# sensorboard_radiation_rev0.net
KiCad netlist of a schematic drawn in EAGLE
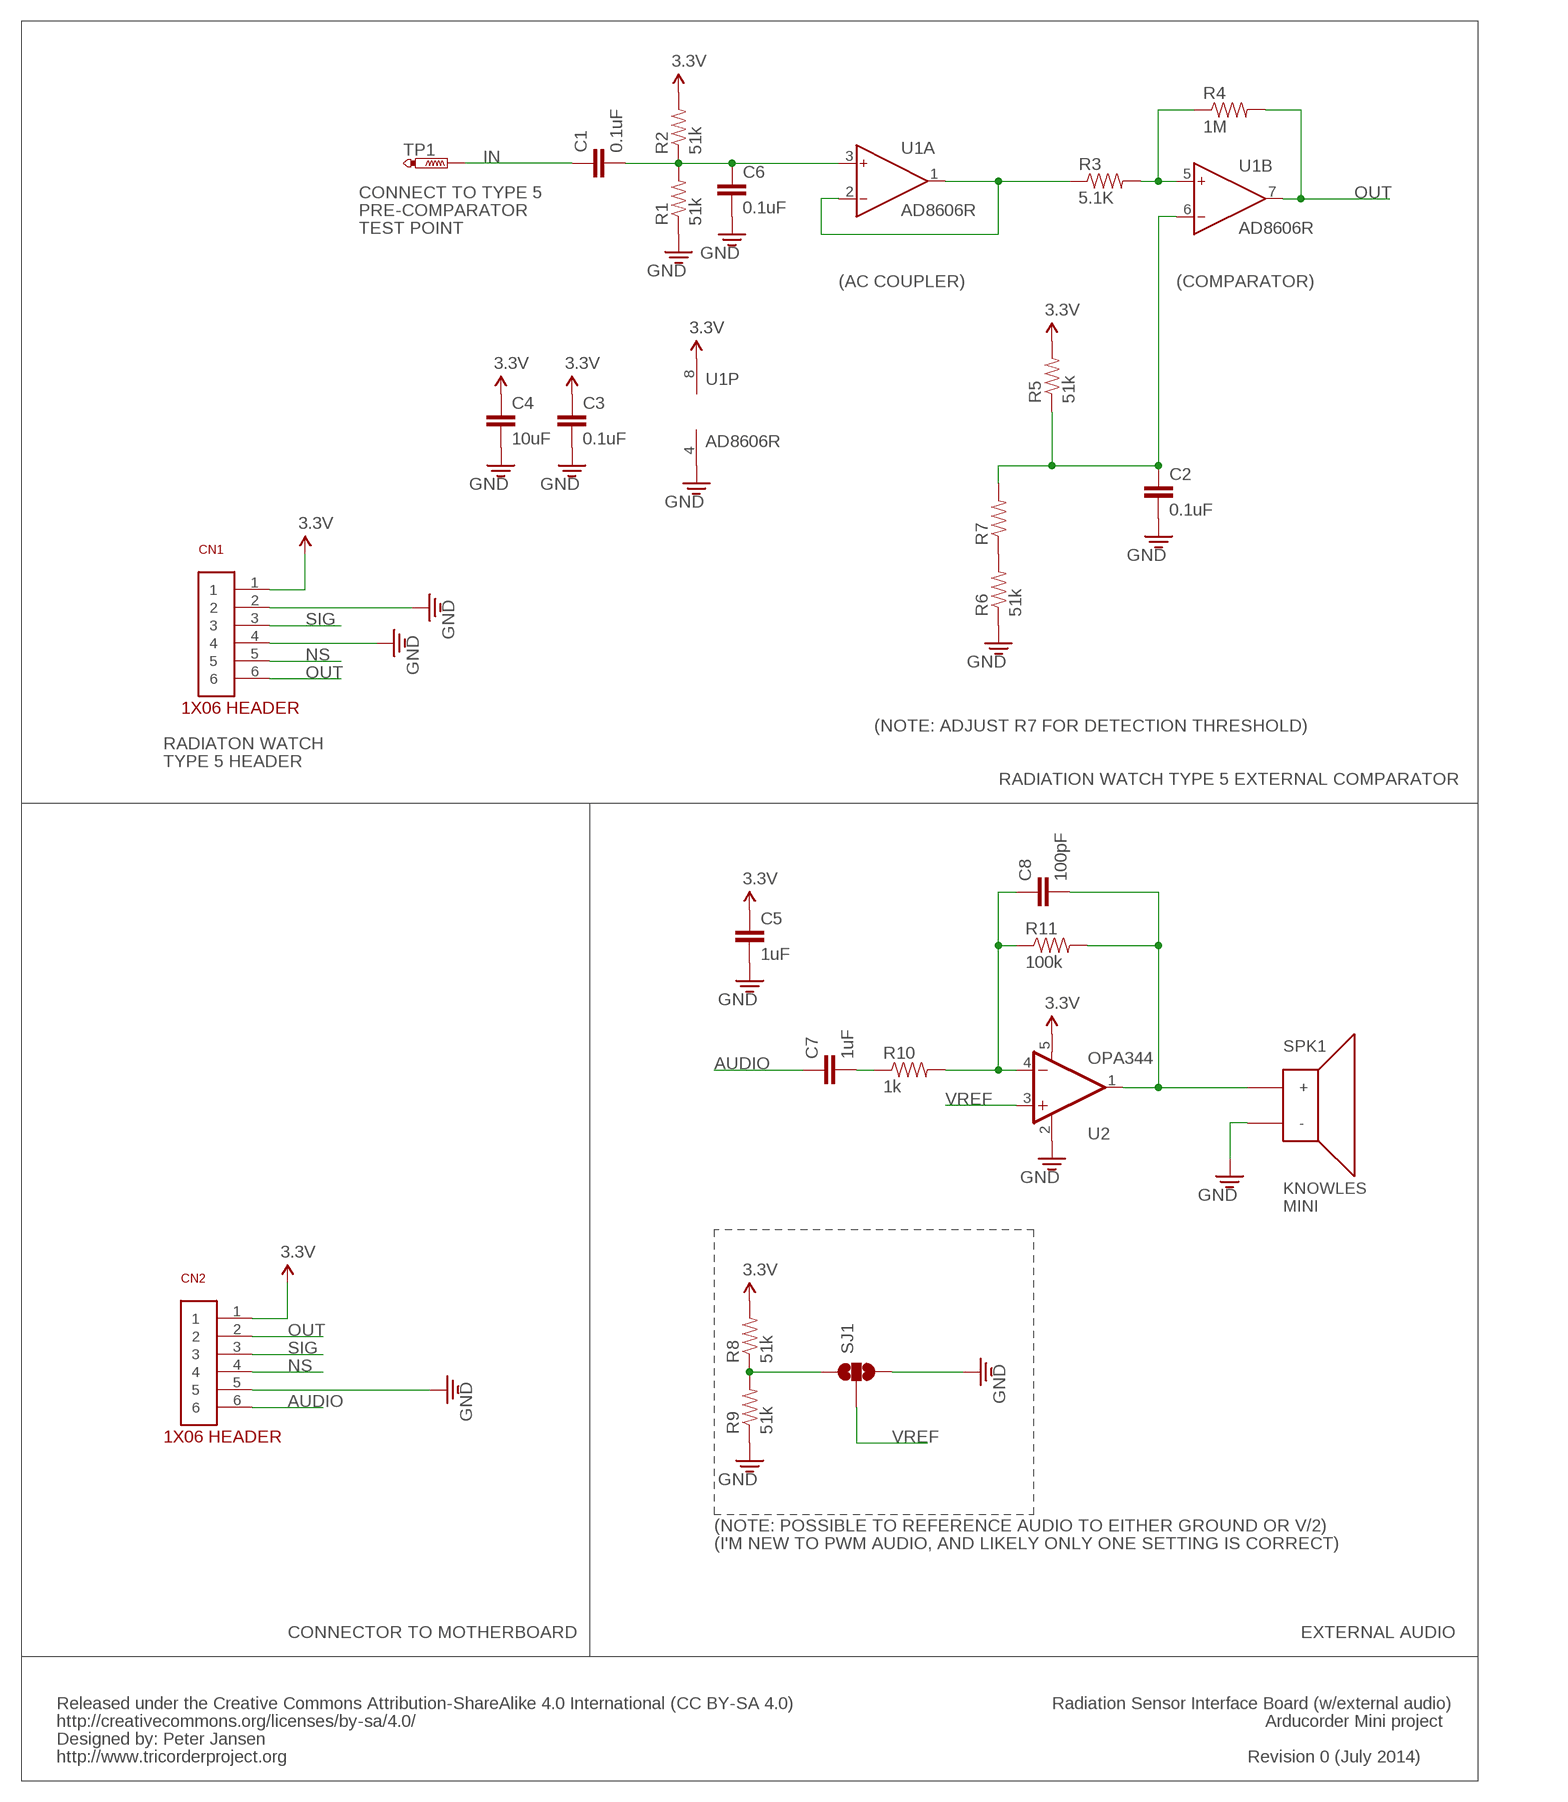
[diagram p0: schematic, sheet 1]

(export (version "E")
  (design (tool "Eeschema 10.0.6"))
  (components
    (comp (ref "C1")
      (value "0.1uF")
      (footprint "eagle-import:0603")
      (libsource (lib "eagle-import") (part "CAP0603"))
    )
    (comp (ref "C2")
      (value "0.1uF")
      (footprint "eagle-import:0603")
      (libsource (lib "eagle-import") (part "CAP0603"))
    )
    (comp (ref "C3")
      (value "0.1uF")
      (footprint "eagle-import:0603")
      (libsource (lib "eagle-import") (part "CAP0603"))
    )
    (comp (ref "C4")
      (value "10uF")
      (footprint "eagle-import:0603")
      (libsource (lib "eagle-import") (part "CAP0603"))
    )
    (comp (ref "C5")
      (value "1uF")
      (footprint "eagle-import:0603")
      (libsource (lib "eagle-import") (part "notes_mark5a_CAP0603"))
    )
    (comp (ref "C6")
      (value "0.1uF")
      (footprint "eagle-import:0603")
      (libsource (lib "eagle-import") (part "CAP0603"))
    )
    (comp (ref "C7")
      (value "1uF")
      (footprint "eagle-import:0603")
      (libsource (lib "eagle-import") (part "notes_mark5a_CAP0603"))
    )
    (comp (ref "C8")
      (value "100pF")
      (footprint "eagle-import:0603")
      (libsource (lib "eagle-import") (part "notes_mark5a_CAP0603"))
    )
    (comp (ref "CN1")
      (value "1X06")
      (footprint "eagle-import:1X06")
      (libsource (lib "eagle-import") (part "1X06"))
    )
    (comp (ref "CN2")
      (value "1X06")
      (footprint "eagle-import:1X06")
      (libsource (lib "eagle-import") (part "arm1a_1X06"))
    )
    (comp (ref "R1")
      (value "51k")
      (footprint "eagle-import:0603")
      (libsource (lib "eagle-import") (part "RESISTOR0603"))
    )
    (comp (ref "R2")
      (value "51k")
      (footprint "eagle-import:0603")
      (libsource (lib "eagle-import") (part "RESISTOR0603"))
    )
    (comp (ref "R3")
      (value "5.1K")
      (footprint "eagle-import:0603")
      (libsource (lib "eagle-import") (part "RESISTOR0603"))
    )
    (comp (ref "R4")
      (value "1M")
      (footprint "eagle-import:0603")
      (libsource (lib "eagle-import") (part "RESISTOR0603"))
    )
    (comp (ref "R5")
      (value "51k")
      (footprint "eagle-import:0603")
      (libsource (lib "eagle-import") (part "RESISTOR0603"))
    )
    (comp (ref "R6")
      (value "51k")
      (footprint "eagle-import:0603")
      (libsource (lib "eagle-import") (part "RESISTOR0603"))
    )
    (comp (ref "R7")
      (value "RESISTOR0603")
      (footprint "eagle-import:0603")
      (libsource (lib "eagle-import") (part "RESISTOR0603"))
    )
    (comp (ref "R8")
      (value "51k")
      (footprint "eagle-import:0603")
      (libsource (lib "eagle-import") (part "notes_mark5a_RESISTOR0603"))
    )
    (comp (ref "R9")
      (value "51k")
      (footprint "eagle-import:0603")
      (libsource (lib "eagle-import") (part "notes_mark5a_RESISTOR0603"))
    )
    (comp (ref "R10")
      (value "1k")
      (footprint "eagle-import:0603")
      (libsource (lib "eagle-import") (part "notes_mark5a_RESISTOR0603"))
    )
    (comp (ref "R11")
      (value "100k")
      (footprint "eagle-import:0603")
      (libsource (lib "eagle-import") (part "notes_mark5a_RESISTOR0603"))
    )
    (comp (ref "SJ1")
      (value "SOLDERJUMPER_2WAYPASTE1&2")
      (footprint "eagle-import:SJ_3_PASTE1&2")
      (libsource (lib "eagle-import") (part "SOLDERJUMPER_2WAYPASTE1&2"))
    )
    (comp (ref "SPK1")
      (value "KNOWLES-MINI-SPEAKER")
      (footprint "eagle-import:KNOWLES-MINI-SPEAKER")
      (libsource (lib "eagle-import") (part "KNOWLES-MINI-SPEAKER"))
    )
    (comp (ref "TP1")
      (value "PTR1PAD1-13")
      (footprint "eagle-import:P1-13")
      (libsource (lib "eagle-import") (part "PTR1PAD1-13"))
    )
    (comp (ref "U1")
      (value "AD8606R")
      (footprint "eagle-import:SO8")
      (fields (field (name "MPN") "AD8607ARMZ-R2"))
      (libsource (lib "eagle-import") (part "AD8607R"))
    )
    (comp (ref "U2")
      (value "OPA344")
      (footprint "eagle-import:SOT23-5")
      (libsource (lib "eagle-import") (part "OPA344"))
    )
  )
  (nets
    (net (code "1") (name "/AUDIO") (class "Default")
      (node (ref "C7") (pin "1") (pinfunction "1_1") (pintype "passive"))
      (node (ref "CN2") (pin "6") (pinfunction "6_6") (pintype "bidirectional"))
    )
    (net (code "2") (name "/IN") (class "Default")
      (node (ref "C1") (pin "1") (pinfunction "1_1") (pintype "passive"))
      (node (ref "TP1") (pin "TP") (pinfunction "TP_TP") (pintype "input"))
    )
    (net (code "3") (name "/NS") (class "Default")
      (node (ref "CN1") (pin "5") (pinfunction "5_5") (pintype "bidirectional"))
      (node (ref "CN2") (pin "4") (pinfunction "4_4") (pintype "bidirectional"))
    )
    (net (code "4") (name "/OUT") (class "Default")
      (node (ref "CN1") (pin "6") (pinfunction "6_6") (pintype "bidirectional"))
      (node (ref "CN2") (pin "2") (pinfunction "2_2") (pintype "bidirectional"))
      (node (ref "R4") (pin "2") (pinfunction "2_2") (pintype "passive"))
      (node (ref "U1") (pin "7") (pinfunction "OUT_7") (pintype "output"))
    )
    (net (code "5") (name "/SIG") (class "Default")
      (node (ref "CN1") (pin "3") (pinfunction "3_3") (pintype "bidirectional"))
      (node (ref "CN2") (pin "3") (pinfunction "3_3") (pintype "bidirectional"))
    )
    (net (code "6") (name "/VREF") (class "Default")
      (node (ref "SJ1") (pin "2") (pinfunction "2_2") (pintype "passive"))
      (node (ref "U2") (pin "3") (pinfunction "+IN_3") (pintype "input"))
    )
    (net (code "7") (name "3.3V") (class "Default")
      (node (ref "C3") (pin "1") (pinfunction "1_1") (pintype "passive"))
      (node (ref "C4") (pin "1") (pinfunction "1_1") (pintype "passive"))
      (node (ref "C5") (pin "1") (pinfunction "1_1") (pintype "passive"))
      (node (ref "CN1") (pin "1") (pinfunction "1_1") (pintype "bidirectional"))
      (node (ref "CN2") (pin "1") (pinfunction "1_1") (pintype "bidirectional"))
      (node (ref "R2") (pin "2") (pinfunction "2_2") (pintype "passive"))
      (node (ref "R5") (pin "2") (pinfunction "2_2") (pintype "passive"))
      (node (ref "R8") (pin "2") (pinfunction "2_2") (pintype "passive"))
      (node (ref "U1") (pin "8") (pinfunction "V+_8") (pintype "power_in"))
      (node (ref "U2") (pin "5") (pinfunction "V+_5") (pintype "power_in"))
    )
    (net (code "8") (name "GND") (class "Default")
      (node (ref "C2") (pin "2") (pinfunction "2_2") (pintype "passive"))
      (node (ref "C3") (pin "2") (pinfunction "2_2") (pintype "passive"))
      (node (ref "C4") (pin "2") (pinfunction "2_2") (pintype "passive"))
      (node (ref "C5") (pin "2") (pinfunction "2_2") (pintype "passive"))
      (node (ref "C6") (pin "2") (pinfunction "2_2") (pintype "passive"))
      (node (ref "CN1") (pin "2") (pinfunction "2_2") (pintype "bidirectional"))
      (node (ref "CN1") (pin "4") (pinfunction "4_4") (pintype "bidirectional"))
      (node (ref "CN2") (pin "5") (pinfunction "5_5") (pintype "bidirectional"))
      (node (ref "R1") (pin "1") (pinfunction "1_1") (pintype "passive"))
      (node (ref "R6") (pin "1") (pinfunction "1_1") (pintype "passive"))
      (node (ref "R9") (pin "1") (pinfunction "1_1") (pintype "passive"))
      (node (ref "SJ1") (pin "3") (pinfunction "3_3") (pintype "passive"))
      (node (ref "SPK1") (pin "NEG") (pinfunction "-_NEG") (pintype "bidirectional"))
      (node (ref "U1") (pin "4") (pinfunction "V-_4") (pintype "power_in"))
      (node (ref "U2") (pin "2") (pinfunction "V-_2") (pintype "power_in"))
    )
    (net (code "9") (name "Net-(C7-Pad2)") (class "Default")
      (node (ref "C7") (pin "2") (pinfunction "2_2") (pintype "passive"))
      (node (ref "R10") (pin "1") (pinfunction "1_1") (pintype "passive"))
    )
    (net (code "10") (name "Net-(R6-Pad2)") (class "Default")
      (node (ref "R6") (pin "2") (pinfunction "2_2") (pintype "passive"))
      (node (ref "R7") (pin "1") (pinfunction "1_1") (pintype "passive"))
    )
    (net (code "11") (name "Net-(R8-Pad1)") (class "Default")
      (node (ref "R8") (pin "1") (pinfunction "1_1") (pintype "passive"))
      (node (ref "R9") (pin "2") (pinfunction "2_2") (pintype "passive"))
      (node (ref "SJ1") (pin "1") (pinfunction "1_1") (pintype "passive"))
    )
    (net (code "12") (name "Net-(SPK1-+)") (class "Default")
      (node (ref "C8") (pin "2") (pinfunction "2_2") (pintype "passive"))
      (node (ref "R11") (pin "2") (pinfunction "2_2") (pintype "passive"))
      (node (ref "SPK1") (pin "POS") (pinfunction "+_POS") (pintype "bidirectional"))
      (node (ref "U2") (pin "1") (pinfunction "OUT_1") (pintype "output"))
    )
    (net (code "13") (name "Net-(U1A-IN+)") (class "Default")
      (node (ref "C1") (pin "2") (pinfunction "2_2") (pintype "passive"))
      (node (ref "C6") (pin "1") (pinfunction "1_1") (pintype "passive"))
      (node (ref "R1") (pin "2") (pinfunction "2_2") (pintype "passive"))
      (node (ref "R2") (pin "1") (pinfunction "1_1") (pintype "passive"))
      (node (ref "U1") (pin "3") (pinfunction "IN+_3") (pintype "input"))
    )
    (net (code "14") (name "Net-(U1A-IN-)") (class "Default")
      (node (ref "R3") (pin "1") (pinfunction "1_1") (pintype "passive"))
      (node (ref "U1") (pin "1") (pinfunction "OUT_1") (pintype "output"))
      (node (ref "U1") (pin "2") (pinfunction "IN-_2") (pintype "input"))
    )
    (net (code "15") (name "Net-(U1B-IN+)") (class "Default")
      (node (ref "R3") (pin "2") (pinfunction "2_2") (pintype "passive"))
      (node (ref "R4") (pin "1") (pinfunction "1_1") (pintype "passive"))
      (node (ref "U1") (pin "5") (pinfunction "IN+_5") (pintype "input"))
    )
    (net (code "16") (name "Net-(U1B-IN-)") (class "Default")
      (node (ref "C2") (pin "1") (pinfunction "1_1") (pintype "passive"))
      (node (ref "R5") (pin "1") (pinfunction "1_1") (pintype "passive"))
      (node (ref "R7") (pin "2") (pinfunction "2_2") (pintype "passive"))
      (node (ref "U1") (pin "6") (pinfunction "IN-_6") (pintype "input"))
    )
    (net (code "17") (name "Net-(U2--IN)") (class "Default")
      (node (ref "C8") (pin "1") (pinfunction "1_1") (pintype "passive"))
      (node (ref "R10") (pin "2") (pinfunction "2_2") (pintype "passive"))
      (node (ref "R11") (pin "1") (pinfunction "1_1") (pintype "passive"))
      (node (ref "U2") (pin "4") (pinfunction "-IN_4") (pintype "input"))
    )
  )
)
